# Board_B_SCH.net
KiCad netlist of a schematic drawn in Altium Designer
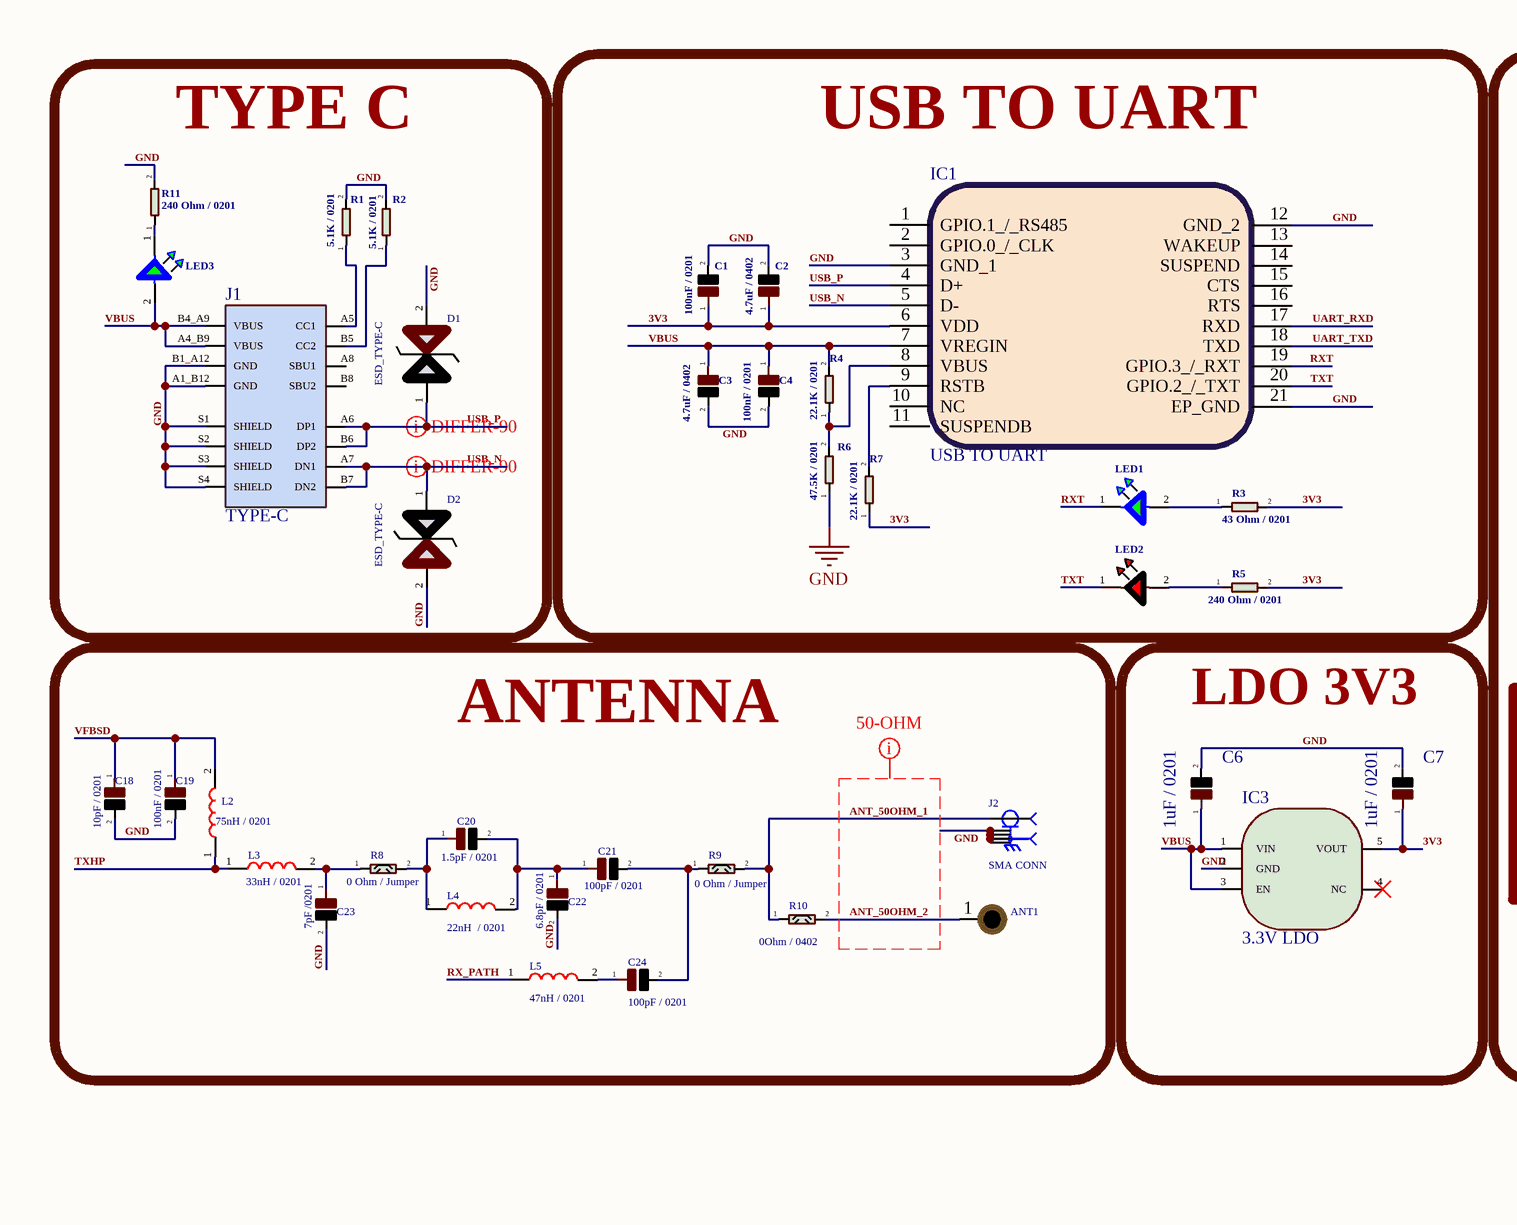
[diagram p0: Board_B_SCH.SchDoc, left]
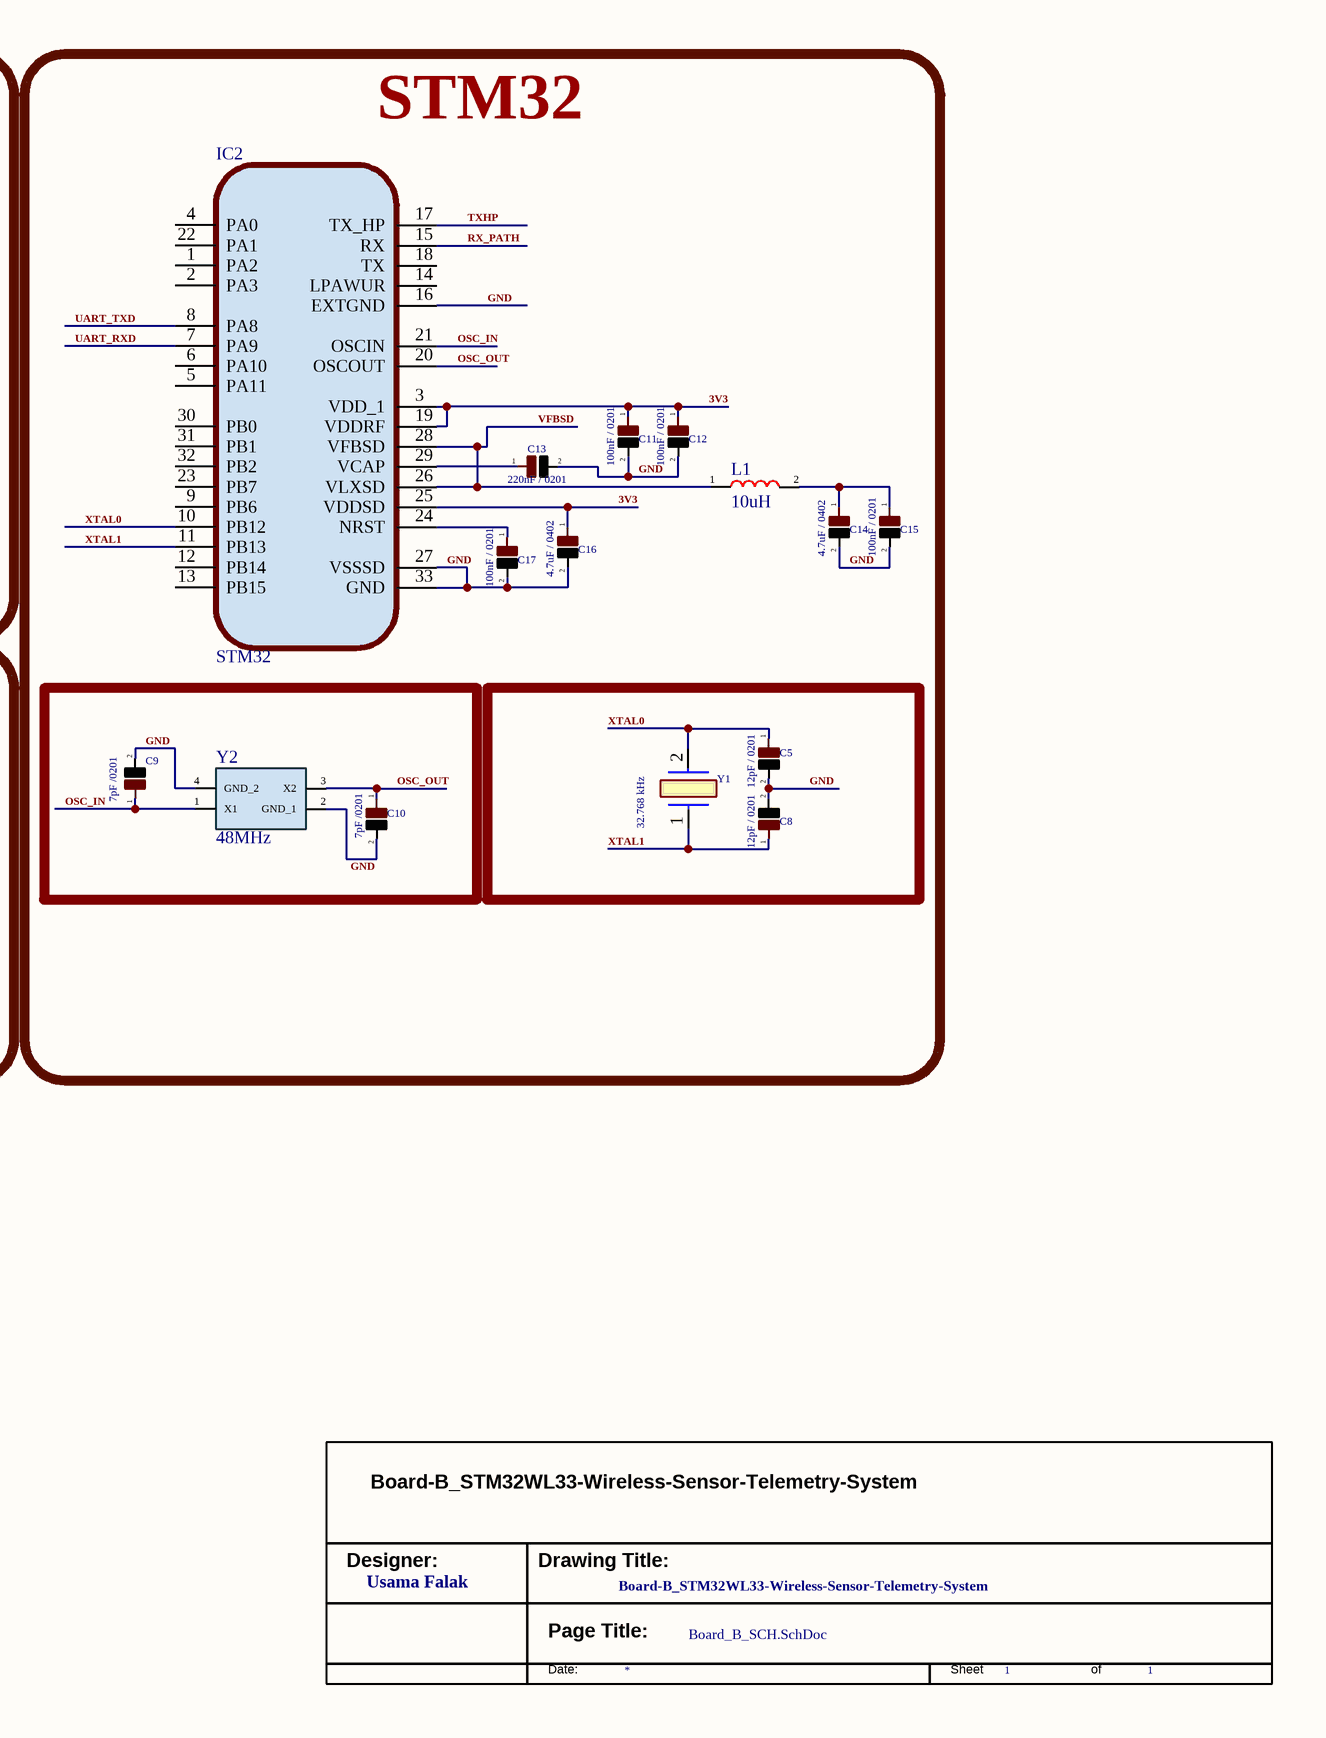
[diagram p1: Board_B_SCH.SchDoc, right]

(export (version "E")
  (design (tool "Eeschema 10.0.6"))
  (components
    (comp (ref "*") (value "TitleBlock_MCPG_B") (libsource (lib "Sensor-SCHLIB") (part "TitleBlock_MCPG_B")))
    (comp (ref "ANT1")
      (value "PAD")
      (footprint "ANTENNA-PAD")
      (libsource (lib "Sensor-SCHLIB") (part "ANTENNA-PAD"))
    )
    (comp (ref "C1")
      (value "100nF / 0201")
      (footprint "Sensor-PCBLIB:CAPC-C0201")
      (description "Multilayer Ceramic Capacitors MLCC - SMD/SMT 0.1 uF 16 VDC 10% 0201 X7R")
      (fields
        (field (name "MANUFACTURER_PART_NUMBER") "GRM033Z71C104KE14J")
        (field (name "MOUSER PART NUMBER") "81-GRM033Z71C104KE4J")
      )
      (libsource (lib "") (part "GRM033Z71C104KE14J_1"))
    )
    (comp (ref "C2")
      (value "4.7uF / 0402")
      (footprint "Sensor-PCBLIB:CAPC-C0402")
      (description "4.7uF ±20% 25V Ceramic Capacitor 0402")
      (fields
        (field (name "MANUFACTURER_PART_NUMBER") "GRM155C61E475ME15J")
        (field (name "MOUSER PART NUMBER") "81-GRM15C61E475ME15J")
      )
      (libsource (lib "") (part "GRM155C61E475ME15J_1"))
    )
    (comp (ref "C3")
      (value "4.7uF / 0402")
      (footprint "Sensor-PCBLIB:CAPC-C0402")
      (description "4.7uF ±20% 25V Ceramic Capacitor 0402")
      (fields
        (field (name "MANUFACTURER_PART_NUMBER") "GRM155C61E475ME15J")
        (field (name "MOUSER PART NUMBER") "81-GRM15C61E475ME15J")
      )
      (libsource (lib "Sensor-SCHLIB") (part "GRM155C61E475ME15J"))
    )
    (comp (ref "C4")
      (value "100nF / 0201")
      (footprint "Sensor-PCBLIB:CAPC-C0201")
      (description "Multilayer Ceramic Capacitors MLCC - SMD/SMT 0.1 uF 16 VDC 10% 0201 X7R")
      (fields
        (field (name "MANUFACTURER_PART_NUMBER") "GRM033Z71C104KE14J")
        (field (name "MOUSER PART NUMBER") "81-GRM033Z71C104KE4J")
      )
      (libsource (lib "Sensor-SCHLIB") (part "GRM033Z71C104KE14J"))
    )
    (comp (ref "C5")
      (value "12pF / 0201")
      (footprint "Sensor-PCBLIB:CAPC-C0201")
      (description "12pF ±2% 25V Ceramic Capacitor X6S 0201")
      (fields
        (field (name "MANUFACTURER_PART_NUMBER") "GJM0335C1E120GB01D")
        (field (name "MOUSER PART NUMBER") "81-GJM0335C1E120GB1D")
      )
      (libsource (lib "Sensor-SCHLIB") (part "GJM0335C1E120GB01D"))
    )
    (comp (ref "C6")
      (value "1uF / 0201")
      (footprint "Sensor-PCBLIB:CAPC-C0201")
      (description "Multilayer Ceramic Capacitors MLCC - SMD/SMT 1 uF 16 VDC 20% 0201 X5R")
      (fields
        (field (name "MANUFACTURER_PART_NUMBER") "GRM033R61C105ME15D")
        (field (name "MOUSER PART NUMBER") "81-GRM033R61C105ME5D")
      )
      (libsource (lib "Sensor-SCHLIB") (part "GRM033R61C105ME15D"))
    )
    (comp (ref "C7")
      (value "1uF / 0201")
      (footprint "Sensor-PCBLIB:CAPC-C0201")
      (description "Multilayer Ceramic Capacitors MLCC - SMD/SMT 1 uF 16 VDC 20% 0201 X5R")
      (fields
        (field (name "MANUFACTURER_PART_NUMBER") "GRM033R61C105ME15D")
        (field (name "MOUSER PART NUMBER") "81-GRM033R61C105ME5D")
      )
      (libsource (lib "Sensor-SCHLIB") (part "GRM033R61C105ME15D"))
    )
    (comp (ref "C8")
      (value "12pF / 0201")
      (footprint "Sensor-PCBLIB:CAPC-C0201")
      (description "12pF ±2% 25V Ceramic Capacitor X6S 0201")
      (fields
        (field (name "MANUFACTURER_PART_NUMBER") "GJM0335C1E120GB01D")
        (field (name "MOUSER PART NUMBER") "81-GJM0335C1E120GB1D")
      )
      (libsource (lib "") (part "GJM0335C1E120GB01D_1"))
    )
    (comp (ref "C9")
      (value "7pF /0201")
      (footprint "Sensor-PCBLIB:CAPC-C0201")
      (description "7pF 25V Ceramic Capacitor C0G 0201")
      (fields
        (field (name "MANUFACTURER_PART_NUMBER") "GJM0335C1E7R0BB01D")
        (field (name "LCSC-PART#") "C1864565")
      )
      (libsource (lib "Sensor-SCHLIB") (part "GJM0335C1E7R0BB01D"))
    )
    (comp (ref "C10")
      (value "7pF /0201")
      (footprint "Sensor-PCBLIB:CAPC-C0201")
      (description "7pF 25V Ceramic Capacitor C0G 0201")
      (fields
        (field (name "MANUFACTURER_PART_NUMBER") "GJM0335C1E7R0BB01D")
        (field (name "LCSC-PART#") "C1864565")
      )
      (libsource (lib "") (part "GJM0335C1E7R0BB01D_1"))
    )
    (comp (ref "C11")
      (value "100nF / 0201")
      (footprint "Sensor-PCBLIB:CAPC-C0201")
      (description "Multilayer Ceramic Capacitors MLCC - SMD/SMT 0.1 uF 16 VDC 10% 0201 X7R")
      (fields
        (field (name "MANUFACTURER_PART_NUMBER") "GRM033Z71C104KE14J")
        (field (name "MOUSER PART NUMBER") "81-GRM033Z71C104KE4J")
      )
      (libsource (lib "Sensor-SCHLIB") (part "GRM033Z71C104KE14J"))
    )
    (comp (ref "C12")
      (value "100nF / 0201")
      (footprint "Sensor-PCBLIB:CAPC-C0201")
      (description "Multilayer Ceramic Capacitors MLCC - SMD/SMT 0.1 uF 16 VDC 10% 0201 X7R")
      (fields
        (field (name "MANUFACTURER_PART_NUMBER") "GRM033Z71C104KE14J")
        (field (name "MOUSER PART NUMBER") "81-GRM033Z71C104KE4J")
      )
      (libsource (lib "Sensor-SCHLIB") (part "GRM033Z71C104KE14J"))
    )
    (comp (ref "C13")
      (value "220nF / 0201")
      (footprint "Sensor-PCBLIB:CAPC-C0201")
      (description "220nF X6S ±10% 10V 0201 Ceramic Capacitors RoHS")
      (fields
        (field (name "MANUFACTURER_PART_NUMBER") "GRM033C81A224KE01D")
        (field (name "LCSC-PART#") "C20044506")
      )
      (libsource (lib "Sensor-SCHLIB") (part "GRM033C81A224KE01D"))
    )
    (comp (ref "C14")
      (value "4.7uF / 0402")
      (footprint "Sensor-PCBLIB:CAPC-C0402")
      (description "4.7uF ±20% 25V Ceramic Capacitor 0402")
      (fields
        (field (name "MANUFACTURER_PART_NUMBER") "GRM155C61E475ME15J")
        (field (name "MOUSER PART NUMBER") "81-GRM15C61E475ME15J")
      )
      (libsource (lib "Sensor-SCHLIB") (part "GRM155C61E475ME15J"))
    )
    (comp (ref "C15")
      (value "100nF / 0201")
      (footprint "Sensor-PCBLIB:CAPC-C0201")
      (description "Multilayer Ceramic Capacitors MLCC - SMD/SMT 0.1 uF 16 VDC 10% 0201 X7R")
      (fields
        (field (name "MANUFACTURER_PART_NUMBER") "GRM033Z71C104KE14J")
        (field (name "MOUSER PART NUMBER") "81-GRM033Z71C104KE4J")
      )
      (libsource (lib "Sensor-SCHLIB") (part "GRM033Z71C104KE14J"))
    )
    (comp (ref "C16")
      (value "4.7uF / 0402")
      (footprint "Sensor-PCBLIB:CAPC-C0402")
      (description "4.7uF ±20% 25V Ceramic Capacitor 0402")
      (fields
        (field (name "MANUFACTURER_PART_NUMBER") "GRM155C61E475ME15J")
        (field (name "MOUSER PART NUMBER") "81-GRM15C61E475ME15J")
      )
      (libsource (lib "Sensor-SCHLIB") (part "GRM155C61E475ME15J"))
    )
    (comp (ref "C17")
      (value "100nF / 0201")
      (footprint "Sensor-PCBLIB:CAPC-C0201")
      (description "Multilayer Ceramic Capacitors MLCC - SMD/SMT 0.1 uF 16 VDC 10% 0201 X7R")
      (fields
        (field (name "MANUFACTURER_PART_NUMBER") "GRM033Z71C104KE14J")
        (field (name "MOUSER PART NUMBER") "81-GRM033Z71C104KE4J")
      )
      (libsource (lib "Sensor-SCHLIB") (part "GRM033Z71C104KE14J"))
    )
    (comp (ref "C18")
      (value "10pF / 0201")
      (footprint "Sensor-PCBLIB:CAPC-C0201")
      (description "10pF ±2% 25V Ceramic Capacitor C0G 0201")
      (fields
        (field (name "MANUFACTURER_PART_NUMBER") "GJM0335C1E100GB01D")
        (field (name "MOUSER PART NUMBER") "81-GJM0335C1E100GB1D")
      )
      (libsource (lib "Sensor-SCHLIB") (part "GJM0335C1E100GB01D"))
    )
    (comp (ref "C19")
      (value "100nF / 0201")
      (footprint "Sensor-PCBLIB:CAPC-C0201")
      (description "Multilayer Ceramic Capacitors MLCC - SMD/SMT 0.1 uF 16 VDC 10% 0201 X7R")
      (fields
        (field (name "MANUFACTURER_PART_NUMBER") "GRM033Z71C104KE14J")
        (field (name "MOUSER PART NUMBER") "81-GRM033Z71C104KE4J")
      )
      (libsource (lib "Sensor-SCHLIB") (part "GRM033Z71C104KE14J"))
    )
    (comp (ref "C20")
      (value "1.5pF / 0201")
      (footprint "Sensor-PCBLIB:CAPC-C0201")
      (description "1.5pF 25V Ceramic Capacitor C0G 0201")
      (fields
        (field (name "MANUFACTURER_PART_NUMBER") "GJM0335C1E1R5WB01D")
        (field (name "MOUSER PART NUMBER") "81-GJM0335C1E1R5WB1D")
      )
      (libsource (lib "Sensor-SCHLIB") (part "GJM0335C1E1R5WB01D"))
    )
    (comp (ref "C21")
      (value "100pF / 0201")
      (footprint "Sensor-PCBLIB:CAPC-C0201")
      (description "Multilayer Ceramic Capacitors MLCC - SMD/SMT 100 pF 25 VDC 1% 0201 C0G (NP0)")
      (fields
        (field (name "MANUFACTURER_PART_NUMBER") "GRM0335C1E101FA01D")
        (field (name "MOUSER PART NUMBER") "81-GRM0335C1E101FA1D")
      )
      (libsource (lib "Sensor-SCHLIB") (part "GRM0335C1E101FA01D"))
    )
    (comp (ref "C22")
      (value "6.8pF / 0201")
      (footprint "Sensor-PCBLIB:CAPC-C0201")
      (description "Multilayer Ceramic Capacitors MLCC - SMD/SMT 6.8 pF 25 VDC 0.25 pF 0201 C0G (NP0)")
      (fields
        (field (name "MANUFACTURER_PART_NUMBER") "GJM0335C1E6R8CB01D")
        (field (name "LCSC-PART#") "C415404")
      )
      (libsource (lib "Sensor-SCHLIB") (part "GJM0335C1E6R8CB01D"))
    )
    (comp (ref "C23")
      (value "7pF /0201")
      (footprint "Sensor-PCBLIB:CAPC-C0201")
      (description "7pF 25V Ceramic Capacitor C0G 0201")
      (fields
        (field (name "MANUFACTURER_PART_NUMBER") "GJM0335C1E7R0BB01D")
        (field (name "LCSC-PART#") "C1864565")
      )
      (libsource (lib "") (part "GJM0335C1E7R0BB01D_1"))
    )
    (comp (ref "C24")
      (value "100pF / 0201")
      (footprint "Sensor-PCBLIB:CAPC-C0201")
      (description "Multilayer Ceramic Capacitors MLCC - SMD/SMT 100 pF 25 VDC 1% 0201 C0G (NP0)")
      (fields
        (field (name "MANUFACTURER_PART_NUMBER") "GRM0335C1E101FA01D")
        (field (name "MOUSER PART NUMBER") "81-GRM0335C1E101FA1D")
      )
      (libsource (lib "Sensor-SCHLIB") (part "GRM0335C1E101FA01D"))
    )
    (comp (ref "D1")
      (value "ESD_TYPE-C")
      (footprint "Sensor-PCBLIB:PESD5V0V1BB115")
      (description "ESD Protection Diodes / TVS Diodes The factory is currently not accepting orders for this product.")
      (fields
        (field (name "MANUFACTURER_PART_NUMBER") "PESD5V0V1BB,115")
        (field (name "MOUSER PART NUMBER") "771-PESD5V0V1BB115")
      )
      (libsource (lib "Sensor-SCHLIB") (part "PESD5V0V1BB,115"))
    )
    (comp (ref "D2")
      (value "ESD_TYPE-C")
      (footprint "Sensor-PCBLIB:PESD5V0V1BB115")
      (description "ESD Protection Diodes / TVS Diodes The factory is currently not accepting orders for this product.")
      (fields
        (field (name "MANUFACTURER_PART_NUMBER") "PESD5V0V1BB,115")
        (field (name "MOUSER PART NUMBER") "771-PESD5V0V1BB115")
      )
      (libsource (lib "Sensor-SCHLIB") (part "PESD5V0V1BB,115"))
    )
    (comp (ref "IC1")
      (value "USB TO UART")
      (footprint "Sensor-PCBLIB:CP2102NA02GQFN20")
      (description "USB Bridge, USB to UART USB 2.0 UART Interface 20-QFN (3x3)")
      (fields
        (field (name "MANUFACTURER_PART_NUMBER") "CP2102N-A02-GQFN20R")
        (field (name "MOUSER PART NUMBER") "634-CP2102NA02QFN20R")
      )
      (libsource (lib "Sensor-SCHLIB") (part "CP2102N-A02-GQFN20R"))
    )
    (comp (ref "IC2")
      (value "STM32")
      (footprint "Sensor-PCBLIB:QFN50P500X500X100-33N-D")
      (fields (field (name "MANUFACTURER_PART_NUMBER") "STM32WL33KBV7"))
      (libsource (lib "Sensor-SCHLIB") (part "STM32WL33KBV7"))
    )
    (comp (ref "IC3")
      (value "3.3V LDO")
      (footprint "Sensor-PCBLIB:SOT95P285X140-5N")
      (description "LDO Voltage Regulators 600mA CMOS LDO 50mA 3.3V 250mV")
      (fields
        (field (name "MANUFACTURER_PART_NUMBER") "AP2112K-3.3TRG1")
        (field (name "MOUSER PART NUMBER") "621-AP2112K-3.3TRG1")
      )
      (libsource (lib "Sensor-SCHLIB") (part "AP2112K-3.3TRG1"))
    )
    (comp (ref "J1")
      (value "TYPE-C")
      (footprint "HRO_TYPE-C-31-M-12")
      (description "USB Connectors 24 Receptacle 1 8.94*7.3mm RoHS")
      (fields (field (name "MF") "HRO Electronics Co., Ltd.") (field (name "MP") "TYPE-C-31-M-12"))
      (libsource (lib "Sensor-SCHLIB") (part "TYPE-C-31-M-12"))
    )
    (comp (ref "J2")
      (value "SMA CONN")
      (footprint "SAMTEC_SMA-J-P-H-ST-EM1")
      (fields (field (name "MF") "Samtec") (field (name "MP") "SMA-J-P-H-ST-EM1"))
      (libsource (lib "Sensor-SCHLIB") (part "SMA-J-P-H-ST-EM1"))
    )
    (comp (ref "L1")
      (value "10uH")
      (footprint "Sensor-PCBLIB:IND-C1608X95N")
      (description "10uH 1.05Ω Standard AEC-Q200")
      (fields
        (field (name "MANUFACTURER_PART_NUMBER") "MLZ1608M100WTD25")
        (field (name "MOUSER PART NUMBER") "810-MLZ1608M100WTD25")
      )
      (libsource (lib "Sensor-SCHLIB") (part "MLZ1608M100WTD25"))
    )
    (comp (ref "L2")
      (value "75nH / 0201")
      (footprint "Sensor-PCBLIB:INDC-C0201")
      (description "100mA 75nH ±5% 10Ω 0201 Fixed Inductors RoHS")
      (fields
        (field (name "MANUFACTURER_PART_NUMBER") "LQP03TN75NJ02D")
        (field (name "MOUSER PART NUMBER") "81-LQP03TN75NJ02D")
      )
      (libsource (lib "Sensor-SCHLIB") (part "LQP03TN75NJ02D"))
    )
    (comp (ref "L3")
      (value "33nH / 0201")
      (footprint "Sensor-PCBLIB:INDC-C0201")
      (description "110mA 33nH ±5% 4.25Ω 0201 Fixed Inductors RoHS")
      (fields
        (field (name "MANUFACTURER_PART_NUMBER") "LQP03TG33NJ02D")
        (field (name "MOUSER PART NUMBER") "81-LQP03TG33NJ02D")
      )
      (libsource (lib "Sensor-SCHLIB") (part "LQP03TG33NJ02D"))
    )
    (comp (ref "L4")
      (value "22nH  / 0201")
      (footprint "Sensor-PCBLIB:INDC-C0201")
      (description "140mA 22nH ±5% 2.85Ω Thick Film Inductor 0201 Fixed Inductors RoHS")
      (fields
        (field (name "MANUFACTURER_PART_NUMBER") "LQP03TG22NJ02D")
        (field (name "MOUSER PART NUMBER") "81-LQP03TG22NJ02D")
      )
      (libsource (lib "Sensor-SCHLIB") (part "LQP03TG22NJ02D"))
    )
    (comp (ref "L5")
      (value "47nH / 0201")
      (footprint "Sensor-PCBLIB:IND-0201")
      (description "Inductor")
      (fields
        (field (name "MANUFACTURER_PART_NUMBER") "LQP03HQ47NH02D")
        (field (name "MOUSER PART NUMBER") "81-LQP03HQ47NH02D")
      )
      (libsource (lib "Sensor-SCHLIB") (part "LQP03HQ47NH02D"))
    )
    (comp (ref "LED1")
      (value "GREEN-LED")
      (footprint "Sensor-PCBLIB:LEDC-C0201")
      (description "Emerald Green 525nm LED Indication - Discrete 3.3V 0201")
      (fields (field (name "MANUFACTURER_PART_NUMBER") "XL-0201UGC"))
      (libsource (lib "Sensor-SCHLIB") (part "XL-0201UGC"))
    )
    (comp (ref "LED2")
      (value "RED-LED")
      (footprint "Sensor-PCBLIB:LEDC-C0201")
      (description "Red LED Indication - Discrete 0201")
      (fields (field (name "MANUFACTURER_PART_NUMBER") "XL-0201SURC") (field (name "LCSC-PART#") "C3646923"))
      (libsource (lib "Sensor-SCHLIB") (part "XL-0201SURC"))
    )
    (comp (ref "LED3")
      (value "GREEN-LED")
      (footprint "Sensor-PCBLIB:LEDC-C0201")
      (description "Emerald Green 525nm LED Indication - Discrete 3.3V 0201")
      (fields (field (name "MANUFACTURER_PART_NUMBER") "XL-0201UGC"))
      (libsource (lib "Sensor-SCHLIB") (part "XL-0201UGC"))
    )
    (comp (ref "R1")
      (value "5.1K / 0201")
      (footprint "Sensor-PCBLIB:RESC-C0201")
      (description "5.1kΩ 50mW 25V Thick Film Resistor ±1% ±200ppm/℃ 0201 Chip Resistor - Surface Mount RoHS")
      (fields
        (field (name "MANUFACTURER_PART_NUMBER") "RC0201FR-075K1L")
        (field (name "MOUSER PART NUMBER") "603-RC0201FR-075K1L")
      )
      (libsource (lib "Sensor-SCHLIB") (part "RC0201FR-075K1L"))
    )
    (comp (ref "R2")
      (value "5.1K / 0201")
      (footprint "Sensor-PCBLIB:RESC-C0201")
      (description "5.1kΩ 50mW 25V Thick Film Resistor ±1% ±200ppm/℃ 0201 Chip Resistor - Surface Mount RoHS")
      (fields
        (field (name "MANUFACTURER_PART_NUMBER") "RC0201FR-075K1L")
        (field (name "MOUSER PART NUMBER") "603-RC0201FR-075K1L")
      )
      (libsource (lib "Sensor-SCHLIB") (part "RC0201FR-075K1L"))
    )
    (comp (ref "R3")
      (value "43 Ohm / 0201")
      (footprint "RESC-C0201")
      (description "43Ω ±1% 50mW 0201 Thick Film")
      (fields (field (name "LCSC-PART#") "C226550"))
      (libsource (lib "Sensor-SCHLIB") (part "AC0201FR-0743RL"))
    )
    (comp (ref "R4")
      (value "22.1K / 0201")
      (footprint "RESC-C0201")
      (description "50mW 22.1kΩ 25V Thick Film Resistor ±1% ±200ppm/℃ 0201 Chip Resistor - Surface Mount RoHS")
      (fields (field (name "LCSC-PART#") "C142019"))
      (libsource (lib "Sensor-SCHLIB") (part "RC0201FR-0722K1L"))
    )
    (comp (ref "R5")
      (value "240 Ohm / 0201")
      (footprint "RESC-C0201")
      (description "50mW 240Ω 25V Thick Film Resistor ±1% ±200ppm/℃ 0201 Chip Resistor - Surface Mount RoHS")
      (fields (field (name "LCSC-PART#") "C226476"))
      (libsource (lib "") (part "AC0201FR-07240RL_1"))
    )
    (comp (ref "R6")
      (value "47.5K / 0201")
      (footprint "Sensor-PCBLIB:RESC-C0201")
      (description "50mW 47.5kΩ 30V Thick Film Resistor ±1% ±100ppm/℃ 0201 Chip Resistor - Surface Mount RoHS")
      (fields
        (field (name "MANUFACTURER_PART_NUMBER") "CRCW020147K5FKED")
        (field (name "MOUSER PART NUMBER") "71-CRCW020147K5FKED")
      )
      (libsource (lib "Sensor-SCHLIB") (part "CRCW020147K5FKED"))
    )
    (comp (ref "R7")
      (value "22.1K / 0201")
      (footprint "RESC-C0201")
      (description "50mW 22.1kΩ 25V Thick Film Resistor ±1% ±200ppm/℃ 0201 Chip Resistor - Surface Mount RoHS")
      (fields (field (name "LCSC-PART#") "C142019"))
      (libsource (lib "Sensor-SCHLIB") (part "RC0201FR-0722K1L"))
    )
    (comp (ref "R8")
      (value "0 Ohm / Jumper")
      (footprint "Sensor-PCBLIB:RESC-C0201")
      (description "Resistor")
      (fields
        (field (name "MANUFACTURER_PART_NUMBER") "CRCW02010000Z0ED")
        (field (name "MOUSER PART NUMBER") "71-CRCW02010000Z0ED")
      )
      (libsource (lib "Sensor-SCHLIB") (part "CRCW02010000Z0ED"))
    )
    (comp (ref "R9")
      (value "0 Ohm / Jumper")
      (footprint "Sensor-PCBLIB:RESC-C0201")
      (description "Resistor")
      (fields
        (field (name "MANUFACTURER_PART_NUMBER") "CRCW02010000Z0ED")
        (field (name "MOUSER PART NUMBER") "71-CRCW02010000Z0ED")
      )
      (libsource (lib "Sensor-SCHLIB") (part "CRCW02010000Z0ED"))
    )
    (comp (ref "R10")
      (value "0Ohm / 0402")
      (footprint "Sensor-PCBLIB:RESC-C0402")
      (description "0 Ohms Jumper Chip Resistor 0402 (1005 Metric) Automotive AEC-Q200 Thick Film")
      (fields
        (field (name "MANUFACTURER_PART_NUMBER") "ERJ-2GE0R00X")
        (field (name "MOUSER PART NUMBER") "667-ERJ-2GE0R00X")
      )
      (libsource (lib "Sensor-SCHLIB") (part "ERJ-2GE0R00X"))
    )
    (comp (ref "R11")
      (value "240 Ohm / 0201")
      (footprint "RESC-C0201")
      (description "50mW 240Ω 25V Thick Film Resistor ±1% ±200ppm/℃ 0201 Chip Resistor - Surface Mount RoHS")
      (fields (field (name "LCSC-PART#") "C226476"))
      (libsource (lib "Sensor-SCHLIB") (part "AC0201FR-07240RL"))
    )
    (comp (ref "Y1")
      (value "32.768 kHz")
      (footprint "Sensor-PCBLIB:Q13FC1350000400")
      (description "32.768 kHz ±20ppm Crystal 12.5pF 70 kOhms 2-SMD, No Lead")
      (fields
        (field (name "MANUFACTURER_PART_NUMBER") "Q13FC1350000400")
        (field (name "LCSC-PART#") "C32346")
      )
      (libsource (lib "Sensor-SCHLIB") (part "Q13FC1350000400"))
    )
    (comp (ref "Y2")
      (value "48MHz")
      (footprint "Sensor-PCBLIB:ABM11W300000MHZ4B1UT3")
      (description "Crystal 48MHz ±10ppm 7pF 40Ω SMD2016-4P")
      (fields
        (field (name "MANUFACTURER_PART_NUMBER") "ABM11W-48.0000MHZ-7-B1U-T3")
        (field (name "MOUSER PART NUMBER") "815-11W48-7B1UT")
      )
      (libsource (lib "Sensor-SCHLIB") (part "ABM11W-48.0000MHZ-7-B1U-T3"))
    )
  )
  (nets
    (net (code "1") (name "/3V3") (class "Default")
      (node (ref "C1") (pin "1") (pinfunction "1_1") (pintype "passive"))
      (node (ref "C11") (pin "1") (pinfunction "1_1") (pintype "passive"))
      (node (ref "C12") (pin "1") (pinfunction "1_1") (pintype "passive"))
      (node (ref "C16") (pin "1") (pinfunction "1_1") (pintype "passive"))
      (node (ref "C2") (pin "1") (pinfunction "1_1") (pintype "passive"))
      (node (ref "C7") (pin "1") (pinfunction "1_1") (pintype "passive"))
      (node (ref "IC1") (pin "6") (pinfunction "VDD_6") (pintype "passive"))
      (node (ref "IC2") (pin "19") (pinfunction "VDDRF_19") (pintype "passive"))
      (node (ref "IC2") (pin "25") (pinfunction "VDDSD_25") (pintype "passive"))
      (node (ref "IC2") (pin "3") (pinfunction "VDD_1_3") (pintype "passive"))
      (node (ref "IC3") (pin "5") (pinfunction "VOUT_5") (pintype "passive"))
      (node (ref "R3") (pin "2") (pinfunction "2_2") (pintype "passive"))
      (node (ref "R5") (pin "2") (pinfunction "2_2") (pintype "passive"))
      (node (ref "R7") (pin "1") (pinfunction "1_1") (pintype "passive"))
    )
    (net (code "2") (name "/ANT_50OHM_1") (class "Default")
      (node (ref "J2") (pin "1") (pinfunction "1_1") (pintype "passive"))
      (node (ref "R10") (pin "1") (pinfunction "1_1") (pintype "passive"))
      (node (ref "R9") (pin "2") (pinfunction "2_2") (pintype "passive"))
    )
    (net (code "3") (name "/ANT_50OHM_2") (class "Default")
      (node (ref "ANT1") (pin "1") (pinfunction "0_1") (pintype "passive"))
      (node (ref "R10") (pin "2") (pinfunction "2_2") (pintype "passive"))
    )
    (net (code "4") (name "/OSC_IN") (class "Default")
      (node (ref "C9") (pin "1") (pinfunction "1_1") (pintype "passive"))
      (node (ref "IC2") (pin "21") (pinfunction "OSCIN_21") (pintype "passive"))
      (node (ref "Y2") (pin "1") (pinfunction "X1_1") (pintype "passive"))
    )
    (net (code "5") (name "/OSC_OUT") (class "Default")
      (node (ref "C10") (pin "1") (pinfunction "1_1") (pintype "passive"))
      (node (ref "IC2") (pin "20") (pinfunction "OSCOUT_20") (pintype "passive"))
      (node (ref "Y2") (pin "3") (pinfunction "X2_3") (pintype "passive"))
    )
    (net (code "6") (name "/RXT") (class "Default")
      (node (ref "IC1") (pin "19") (pinfunction "GPIO.3_/_RXT_19") (pintype "passive"))
      (node (ref "LED1") (pin "1") (pinfunction "K_1") (pintype "passive"))
    )
    (net (code "7") (name "/RX_PATH") (class "Default")
      (node (ref "IC2") (pin "15") (pinfunction "RX_15") (pintype "passive"))
      (node (ref "L5") (pin "1") (pinfunction "1_1") (pintype "passive"))
    )
    (net (code "8") (name "/TXHP") (class "Default")
      (node (ref "IC2") (pin "17") (pinfunction "TX_HP_17") (pintype "passive"))
      (node (ref "L2") (pin "1") (pinfunction "1_1") (pintype "passive"))
      (node (ref "L3") (pin "1") (pinfunction "1_1") (pintype "passive"))
    )
    (net (code "9") (name "/TXT") (class "Default")
      (node (ref "IC1") (pin "20") (pinfunction "GPIO.2_/_TXT_20") (pintype "passive"))
      (node (ref "LED2") (pin "1") (pinfunction "K_1") (pintype "passive"))
    )
    (net (code "10") (name "/UART_RXD") (class "Default")
      (node (ref "IC1") (pin "17") (pinfunction "RXD_17") (pintype "passive"))
      (node (ref "IC2") (pin "7") (pinfunction "PA9_7") (pintype "passive"))
    )
    (net (code "11") (name "/UART_TXD") (class "Default")
      (node (ref "IC1") (pin "18") (pinfunction "TXD_18") (pintype "passive"))
      (node (ref "IC2") (pin "8") (pinfunction "PA8_8") (pintype "passive"))
    )
    (net (code "12") (name "/USB_N") (class "Default")
      (node (ref "D2") (pin "1") (pinfunction "K1_1") (pintype "passive"))
      (node (ref "IC1") (pin "5") (pinfunction "D-_5") (pintype "passive"))
      (node (ref "J1") (pin "A7") (pinfunction "DN1_A7") (pintype "passive"))
      (node (ref "J1") (pin "B7") (pinfunction "DN2_B7") (pintype "passive"))
    )
    (net (code "13") (name "/USB_P") (class "Default")
      (node (ref "D1") (pin "1") (pinfunction "K1_1") (pintype "passive"))
      (node (ref "IC1") (pin "4") (pinfunction "D+_4") (pintype "passive"))
      (node (ref "J1") (pin "A6") (pinfunction "DP1_A6") (pintype "passive"))
      (node (ref "J1") (pin "B6") (pinfunction "DP2_B6") (pintype "passive"))
    )
    (net (code "14") (name "/VBUS") (class "Default")
      (node (ref "C3") (pin "1") (pinfunction "1_1") (pintype "passive"))
      (node (ref "C4") (pin "1") (pinfunction "1_1") (pintype "passive"))
      (node (ref "C6") (pin "1") (pinfunction "1_1") (pintype "passive"))
      (node (ref "IC1") (pin "7") (pinfunction "VREGIN_7") (pintype "passive"))
      (node (ref "IC3") (pin "1") (pinfunction "VIN_1") (pintype "passive"))
      (node (ref "IC3") (pin "3") (pinfunction "EN_3") (pintype "passive"))
      (node (ref "J1") (pin "A4_B9") (pinfunction "VBUS_A4_B9") (pintype "passive"))
      (node (ref "J1") (pin "B4_A9") (pinfunction "VBUS_B4_A9") (pintype "passive"))
      (node (ref "LED3") (pin "2") (pinfunction "A_2") (pintype "passive"))
      (node (ref "R4") (pin "2") (pinfunction "2_2") (pintype "passive"))
    )
    (net (code "15") (name "/VFBSD") (class "Default")
      (node (ref "C18") (pin "1") (pinfunction "1_1") (pintype "passive"))
      (node (ref "C19") (pin "1") (pinfunction "1_1") (pintype "passive"))
      (node (ref "IC2") (pin "26") (pinfunction "VLXSD_26") (pintype "passive"))
      (node (ref "IC2") (pin "28") (pinfunction "VFBSD_28") (pintype "passive"))
      (node (ref "L1") (pin "1") (pinfunction "1_1") (pintype "passive"))
      (node (ref "L2") (pin "2") (pinfunction "2_2") (pintype "passive"))
    )
    (net (code "16") (name "/XTAL0") (class "Default")
      (node (ref "C5") (pin "1") (pinfunction "1_1") (pintype "passive"))
      (node (ref "IC2") (pin "10") (pinfunction "PB12_10") (pintype "passive"))
      (node (ref "Y1") (pin "2") (pinfunction "CRYSTAL_2_2") (pintype "passive"))
    )
    (net (code "17") (name "/XTAL1") (class "Default")
      (node (ref "C8") (pin "1") (pinfunction "1_1") (pintype "passive"))
      (node (ref "IC2") (pin "11") (pinfunction "PB13_11") (pintype "passive"))
      (node (ref "Y1") (pin "1") (pintype "passive"))
    )
    (net (code "18") (name "GND") (class "Default")
      (node (ref "C1") (pin "2") (pinfunction "2_2") (pintype "passive"))
      (node (ref "C10") (pin "2") (pinfunction "2_2") (pintype "passive"))
      (node (ref "C11") (pin "2") (pinfunction "2_2") (pintype "passive"))
      (node (ref "C12") (pin "2") (pinfunction "2_2") (pintype "passive"))
      (node (ref "C13") (pin "2") (pinfunction "2_2") (pintype "passive"))
      (node (ref "C14") (pin "2") (pinfunction "2_2") (pintype "passive"))
      (node (ref "C15") (pin "2") (pinfunction "2_2") (pintype "passive"))
      (node (ref "C16") (pin "2") (pinfunction "2_2") (pintype "passive"))
      (node (ref "C17") (pin "2") (pinfunction "2_2") (pintype "passive"))
      (node (ref "C18") (pin "2") (pinfunction "2_2") (pintype "passive"))
      (node (ref "C19") (pin "2") (pinfunction "2_2") (pintype "passive"))
      (node (ref "C2") (pin "2") (pinfunction "2_2") (pintype "passive"))
      (node (ref "C22") (pin "2") (pinfunction "2_2") (pintype "passive"))
      (node (ref "C23") (pin "2") (pinfunction "2_2") (pintype "passive"))
      (node (ref "C3") (pin "2") (pinfunction "2_2") (pintype "passive"))
      (node (ref "C4") (pin "2") (pinfunction "2_2") (pintype "passive"))
      (node (ref "C5") (pin "2") (pinfunction "2_2") (pintype "passive"))
      (node (ref "C6") (pin "2") (pinfunction "2_2") (pintype "passive"))
      (node (ref "C7") (pin "2") (pinfunction "2_2") (pintype "passive"))
      (node (ref "C8") (pin "2") (pinfunction "2_2") (pintype "passive"))
      (node (ref "C9") (pin "2") (pinfunction "2_2") (pintype "passive"))
      (node (ref "D1") (pin "2") (pinfunction "K2_2") (pintype "passive"))
      (node (ref "D2") (pin "2") (pinfunction "K2_2") (pintype "passive"))
      (node (ref "IC1") (pin "12") (pinfunction "GND_2_12") (pintype "passive"))
      (node (ref "IC1") (pin "21") (pinfunction "EP_GND_21") (pintype "passive"))
      (node (ref "IC1") (pin "3") (pinfunction "GND_1_3") (pintype "passive"))
      (node (ref "IC2") (pin "16") (pinfunction "EXTGND_16") (pintype "passive"))
      (node (ref "IC2") (pin "27") (pinfunction "VSSSD_27") (pintype "passive"))
      (node (ref "IC2") (pin "33") (pinfunction "GND_33") (pintype "passive"))
      (node (ref "IC3") (pin "2") (pinfunction "GND_2") (pintype "passive"))
      (node (ref "J1") (pin "A1_B12") (pinfunction "GND_A1_B12") (pintype "passive"))
      (node (ref "J1") (pin "B1_A12") (pinfunction "GND_B1_A12") (pintype "passive"))
      (node (ref "J1") (pin "S1") (pinfunction "SHIELD_S1") (pintype "passive"))
      (node (ref "J1") (pin "S2") (pinfunction "SHIELD_S2") (pintype "passive"))
      (node (ref "J1") (pin "S3") (pinfunction "SHIELD_S3") (pintype "passive"))
      (node (ref "J1") (pin "S4") (pinfunction "SHIELD_S4") (pintype "passive"))
      (node (ref "J2") (pin "2_1") (pinfunction "2_2_1") (pintype "passive"))
      (node (ref "J2") (pin "2_2") (pinfunction "2_2_2") (pintype "passive"))
      (node (ref "J2") (pin "3_1") (pinfunction "2_3_1") (pintype "passive"))
      (node (ref "J2") (pin "3_2") (pinfunction "2_3_2") (pintype "passive"))
      (node (ref "R1") (pin "2") (pinfunction "2_2") (pintype "passive"))
      (node (ref "R11") (pin "2") (pinfunction "2_2") (pintype "passive"))
      (node (ref "R2") (pin "2") (pinfunction "2_2") (pintype "passive"))
      (node (ref "R6") (pin "1") (pinfunction "1_1") (pintype "passive"))
      (node (ref "Y2") (pin "2") (pinfunction "GND_1_2") (pintype "passive"))
      (node (ref "Y2") (pin "4") (pinfunction "GND_2_4") (pintype "passive"))
    )
    (net (code "19") (name "Net-(C14-Pad1)") (class "Default")
      (node (ref "C14") (pin "1") (pinfunction "1_1") (pintype "passive"))
      (node (ref "C15") (pin "1") (pinfunction "1_1") (pintype "passive"))
      (node (ref "L1") (pin "2") (pinfunction "2_2") (pintype "passive"))
    )
    (net (code "20") (name "Net-(C20-Pad1)") (class "Default")
      (node (ref "C20") (pin "1") (pinfunction "1_1") (pintype "passive"))
      (node (ref "L4") (pin "1") (pinfunction "1_1") (pintype "passive"))
      (node (ref "R8") (pin "2") (pinfunction "2_2") (pintype "passive"))
    )
    (net (code "21") (name "Net-(C20-Pad2)") (class "Default")
      (node (ref "C20") (pin "2") (pinfunction "2_2") (pintype "passive"))
      (node (ref "C21") (pin "1") (pinfunction "1_1") (pintype "passive"))
      (node (ref "C22") (pin "1") (pinfunction "1_1") (pintype "passive"))
      (node (ref "L4") (pin "2") (pinfunction "2_2") (pintype "passive"))
    )
    (net (code "22") (name "Net-(C21-Pad2)") (class "Default")
      (node (ref "C21") (pin "2") (pinfunction "2_2") (pintype "passive"))
      (node (ref "C24") (pin "2") (pinfunction "2_2") (pintype "passive"))
      (node (ref "R9") (pin "1") (pinfunction "1_1") (pintype "passive"))
    )
    (net (code "23") (name "Net-(C23-Pad1)") (class "Default")
      (node (ref "C23") (pin "1") (pinfunction "1_1") (pintype "passive"))
      (node (ref "L3") (pin "2") (pinfunction "2_2") (pintype "passive"))
      (node (ref "R8") (pin "1") (pinfunction "1_1") (pintype "passive"))
    )
    (net (code "24") (name "Net-(C24-Pad1)") (class "Default")
      (node (ref "C24") (pin "1") (pinfunction "1_1") (pintype "passive"))
      (node (ref "L5") (pin "2") (pinfunction "2_2") (pintype "passive"))
    )
    (net (code "25") (name "Net-(IC1-RSTB)") (class "Default")
      (node (ref "IC1") (pin "9") (pinfunction "RSTB_9") (pintype "passive"))
      (node (ref "R7") (pin "2") (pinfunction "2_2") (pintype "passive"))
    )
    (net (code "26") (name "Net-(IC1-VBUS)") (class "Default")
      (node (ref "IC1") (pin "8") (pinfunction "VBUS_8") (pintype "passive"))
      (node (ref "R4") (pin "1") (pinfunction "1_1") (pintype "passive"))
      (node (ref "R6") (pin "2") (pinfunction "2_2") (pintype "passive"))
    )
    (net (code "27") (name "Net-(IC2-NRST)") (class "Default")
      (node (ref "C17") (pin "1") (pinfunction "1_1") (pintype "passive"))
      (node (ref "IC2") (pin "24") (pinfunction "NRST_24") (pintype "passive"))
    )
    (net (code "28") (name "Net-(IC2-VCAP)") (class "Default")
      (node (ref "C13") (pin "1") (pinfunction "1_1") (pintype "passive"))
      (node (ref "IC2") (pin "29") (pinfunction "VCAP_29") (pintype "passive"))
    )
    (net (code "29") (name "Net-(J1-CC1)") (class "Default")
      (node (ref "J1") (pin "A5") (pinfunction "CC1_A5") (pintype "passive"))
      (node (ref "R1") (pin "1") (pinfunction "1_1") (pintype "passive"))
    )
    (net (code "30") (name "Net-(J1-CC2)") (class "Default")
      (node (ref "J1") (pin "B5") (pinfunction "CC2_B5") (pintype "passive"))
      (node (ref "R2") (pin "1") (pinfunction "1_1") (pintype "passive"))
    )
    (net (code "31") (name "Net-(LED1-A)") (class "Default")
      (node (ref "LED1") (pin "2") (pinfunction "A_2") (pintype "passive"))
      (node (ref "R3") (pin "1") (pinfunction "1_1") (pintype "passive"))
    )
    (net (code "32") (name "Net-(LED2-A)") (class "Default")
      (node (ref "LED2") (pin "2") (pinfunction "A_2") (pintype "passive"))
      (node (ref "R5") (pin "1") (pinfunction "1_1") (pintype "passive"))
    )
    (net (code "33") (name "Net-(LED3-K)") (class "Default")
      (node (ref "LED3") (pin "1") (pinfunction "K_1") (pintype "passive"))
      (node (ref "R11") (pin "1") (pinfunction "1_1") (pintype "passive"))
    )
    (net (code "34") (name "unconnected-(IC1-CTS-Pad15)") (class "Default")
      (node (ref "IC1") (pin "15") (pinfunction "CTS_15") (pintype "passive"))
    )
    (net (code "35") (name "unconnected-(IC1-GPIO.0_{slash}_CLK-Pad2)") (class "Default")
      (node (ref "IC1") (pin "2") (pinfunction "GPIO.0_/_CLK_2") (pintype "passive"))
    )
    (net (code "36") (name "unconnected-(IC1-GPIO.1_{slash}_RS485-Pad1)") (class "Default")
      (node (ref "IC1") (pin "1") (pinfunction "GPIO.1_/_RS485_1") (pintype "passive"))
    )
    (net (code "37") (name "unconnected-(IC1-NC-Pad10)") (class "Default")
      (node (ref "IC1") (pin "10") (pinfunction "NC_10") (pintype "passive"))
    )
    (net (code "38") (name "unconnected-(IC1-RTS-Pad16)") (class "Default")
      (node (ref "IC1") (pin "16") (pinfunction "RTS_16") (pintype "passive"))
    )
    (net (code "39") (name "unconnected-(IC1-SUSPEND-Pad14)") (class "Default")
      (node (ref "IC1") (pin "14") (pinfunction "SUSPEND_14") (pintype "passive"))
    )
    (net (code "40") (name "unconnected-(IC1-SUSPENDB-Pad11)") (class "Default")
      (node (ref "IC1") (pin "11") (pinfunction "SUSPENDB_11") (pintype "passive"))
    )
    (net (code "41") (name "unconnected-(IC1-WAKEUP-Pad13)") (class "Default")
      (node (ref "IC1") (pin "13") (pinfunction "WAKEUP_13") (pintype "passive"))
    )
    (net (code "42") (name "unconnected-(IC2-LPAWUR-Pad14)") (class "Default")
      (node (ref "IC2") (pin "14") (pinfunction "LPAWUR_14") (pintype "passive"))
    )
    (net (code "43") (name "unconnected-(IC2-PA0-Pad4)") (class "Default")
      (node (ref "IC2") (pin "4") (pinfunction "PA0_4") (pintype "passive"))
    )
    (net (code "44") (name "unconnected-(IC2-PA1-Pad22)") (class "Default")
      (node (ref "IC2") (pin "22") (pinfunction "PA1_22") (pintype "passive"))
    )
    (net (code "45") (name "unconnected-(IC2-PA2-Pad1)") (class "Default")
      (node (ref "IC2") (pin "1") (pinfunction "PA2_1") (pintype "passive"))
    )
    (net (code "46") (name "unconnected-(IC2-PA3-Pad2)") (class "Default")
      (node (ref "IC2") (pin "2") (pinfunction "PA3_2") (pintype "passive"))
    )
    (net (code "47") (name "unconnected-(IC2-PA10-Pad6)") (class "Default")
      (node (ref "IC2") (pin "6") (pinfunction "PA10_6") (pintype "passive"))
    )
    (net (code "48") (name "unconnected-(IC2-PA11-Pad5)") (class "Default")
      (node (ref "IC2") (pin "5") (pinfunction "PA11_5") (pintype "passive"))
    )
    (net (code "49") (name "unconnected-(IC2-PB0-Pad30)") (class "Default")
      (node (ref "IC2") (pin "30") (pinfunction "PB0_30") (pintype "passive"))
    )
    (net (code "50") (name "unconnected-(IC2-PB1-Pad31)") (class "Default")
      (node (ref "IC2") (pin "31") (pinfunction "PB1_31") (pintype "passive"))
    )
    (net (code "51") (name "unconnected-(IC2-PB2-Pad32)") (class "Default")
      (node (ref "IC2") (pin "32") (pinfunction "PB2_32") (pintype "passive"))
    )
    (net (code "52") (name "unconnected-(IC2-PB6-Pad9)") (class "Default")
      (node (ref "IC2") (pin "9") (pinfunction "PB6_9") (pintype "passive"))
    )
    (net (code "53") (name "unconnected-(IC2-PB7-Pad23)") (class "Default")
      (node (ref "IC2") (pin "23") (pinfunction "PB7_23") (pintype "passive"))
    )
    (net (code "54") (name "unconnected-(IC2-PB14-Pad12)") (class "Default")
      (node (ref "IC2") (pin "12") (pinfunction "PB14_12") (pintype "passive"))
    )
    (net (code "55") (name "unconnected-(IC2-PB15-Pad13)") (class "Default")
      (node (ref "IC2") (pin "13") (pinfunction "PB15_13") (pintype "passive"))
    )
    (net (code "56") (name "unconnected-(IC2-TX-Pad18)") (class "Default")
      (node (ref "IC2") (pin "18") (pinfunction "TX_18") (pintype "passive"))
    )
    (net (code "57") (name "unconnected-(IC3-NC-Pad4)") (class "Default")
      (node (ref "IC3") (pin "4") (pinfunction "NC_4") (pintype "passive+no_connect"))
    )
    (net (code "58") (name "unconnected-(J1-SBU1-PadA8)") (class "Default")
      (node (ref "J1") (pin "A8") (pinfunction "SBU1_A8") (pintype "passive"))
    )
    (net (code "59") (name "unconnected-(J1-SBU2-PadB8)") (class "Default")
      (node (ref "J1") (pin "B8") (pinfunction "SBU2_B8") (pintype "passive"))
    )
  )
)
